# PCB.net
KiCad netlist of a schematic drawn in EAGLE
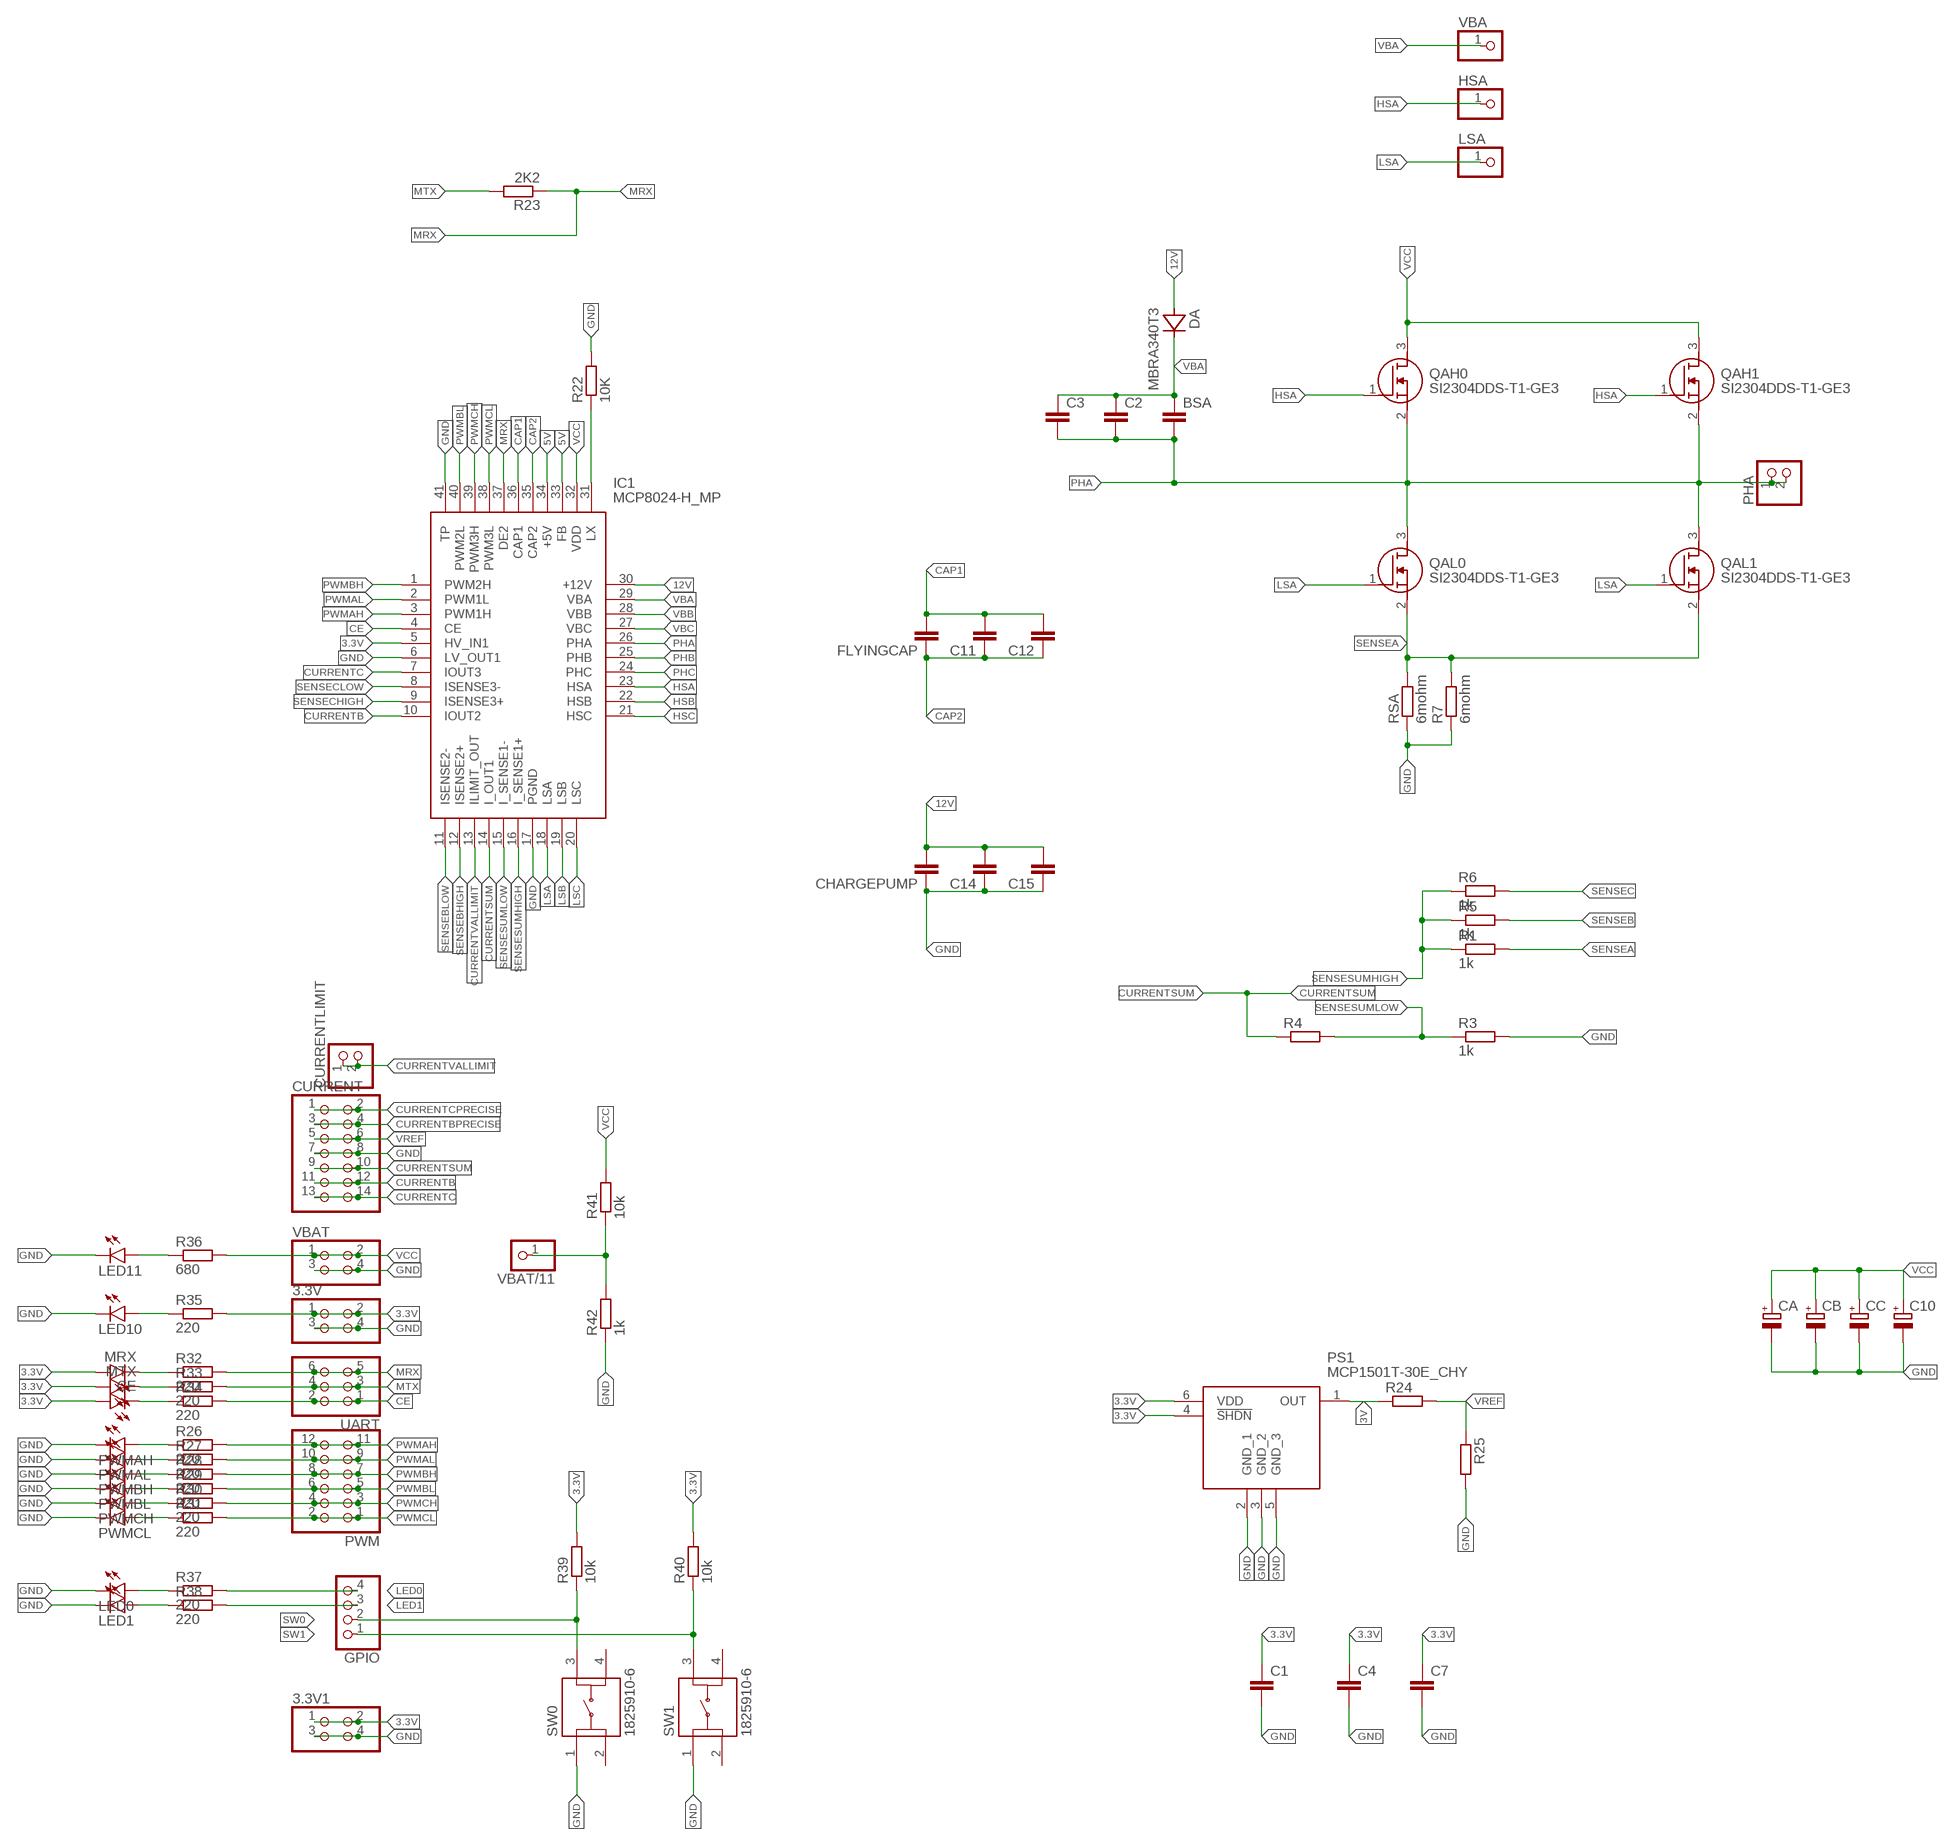
[diagram p0: schematic, sheet 1, part 1 of 2]
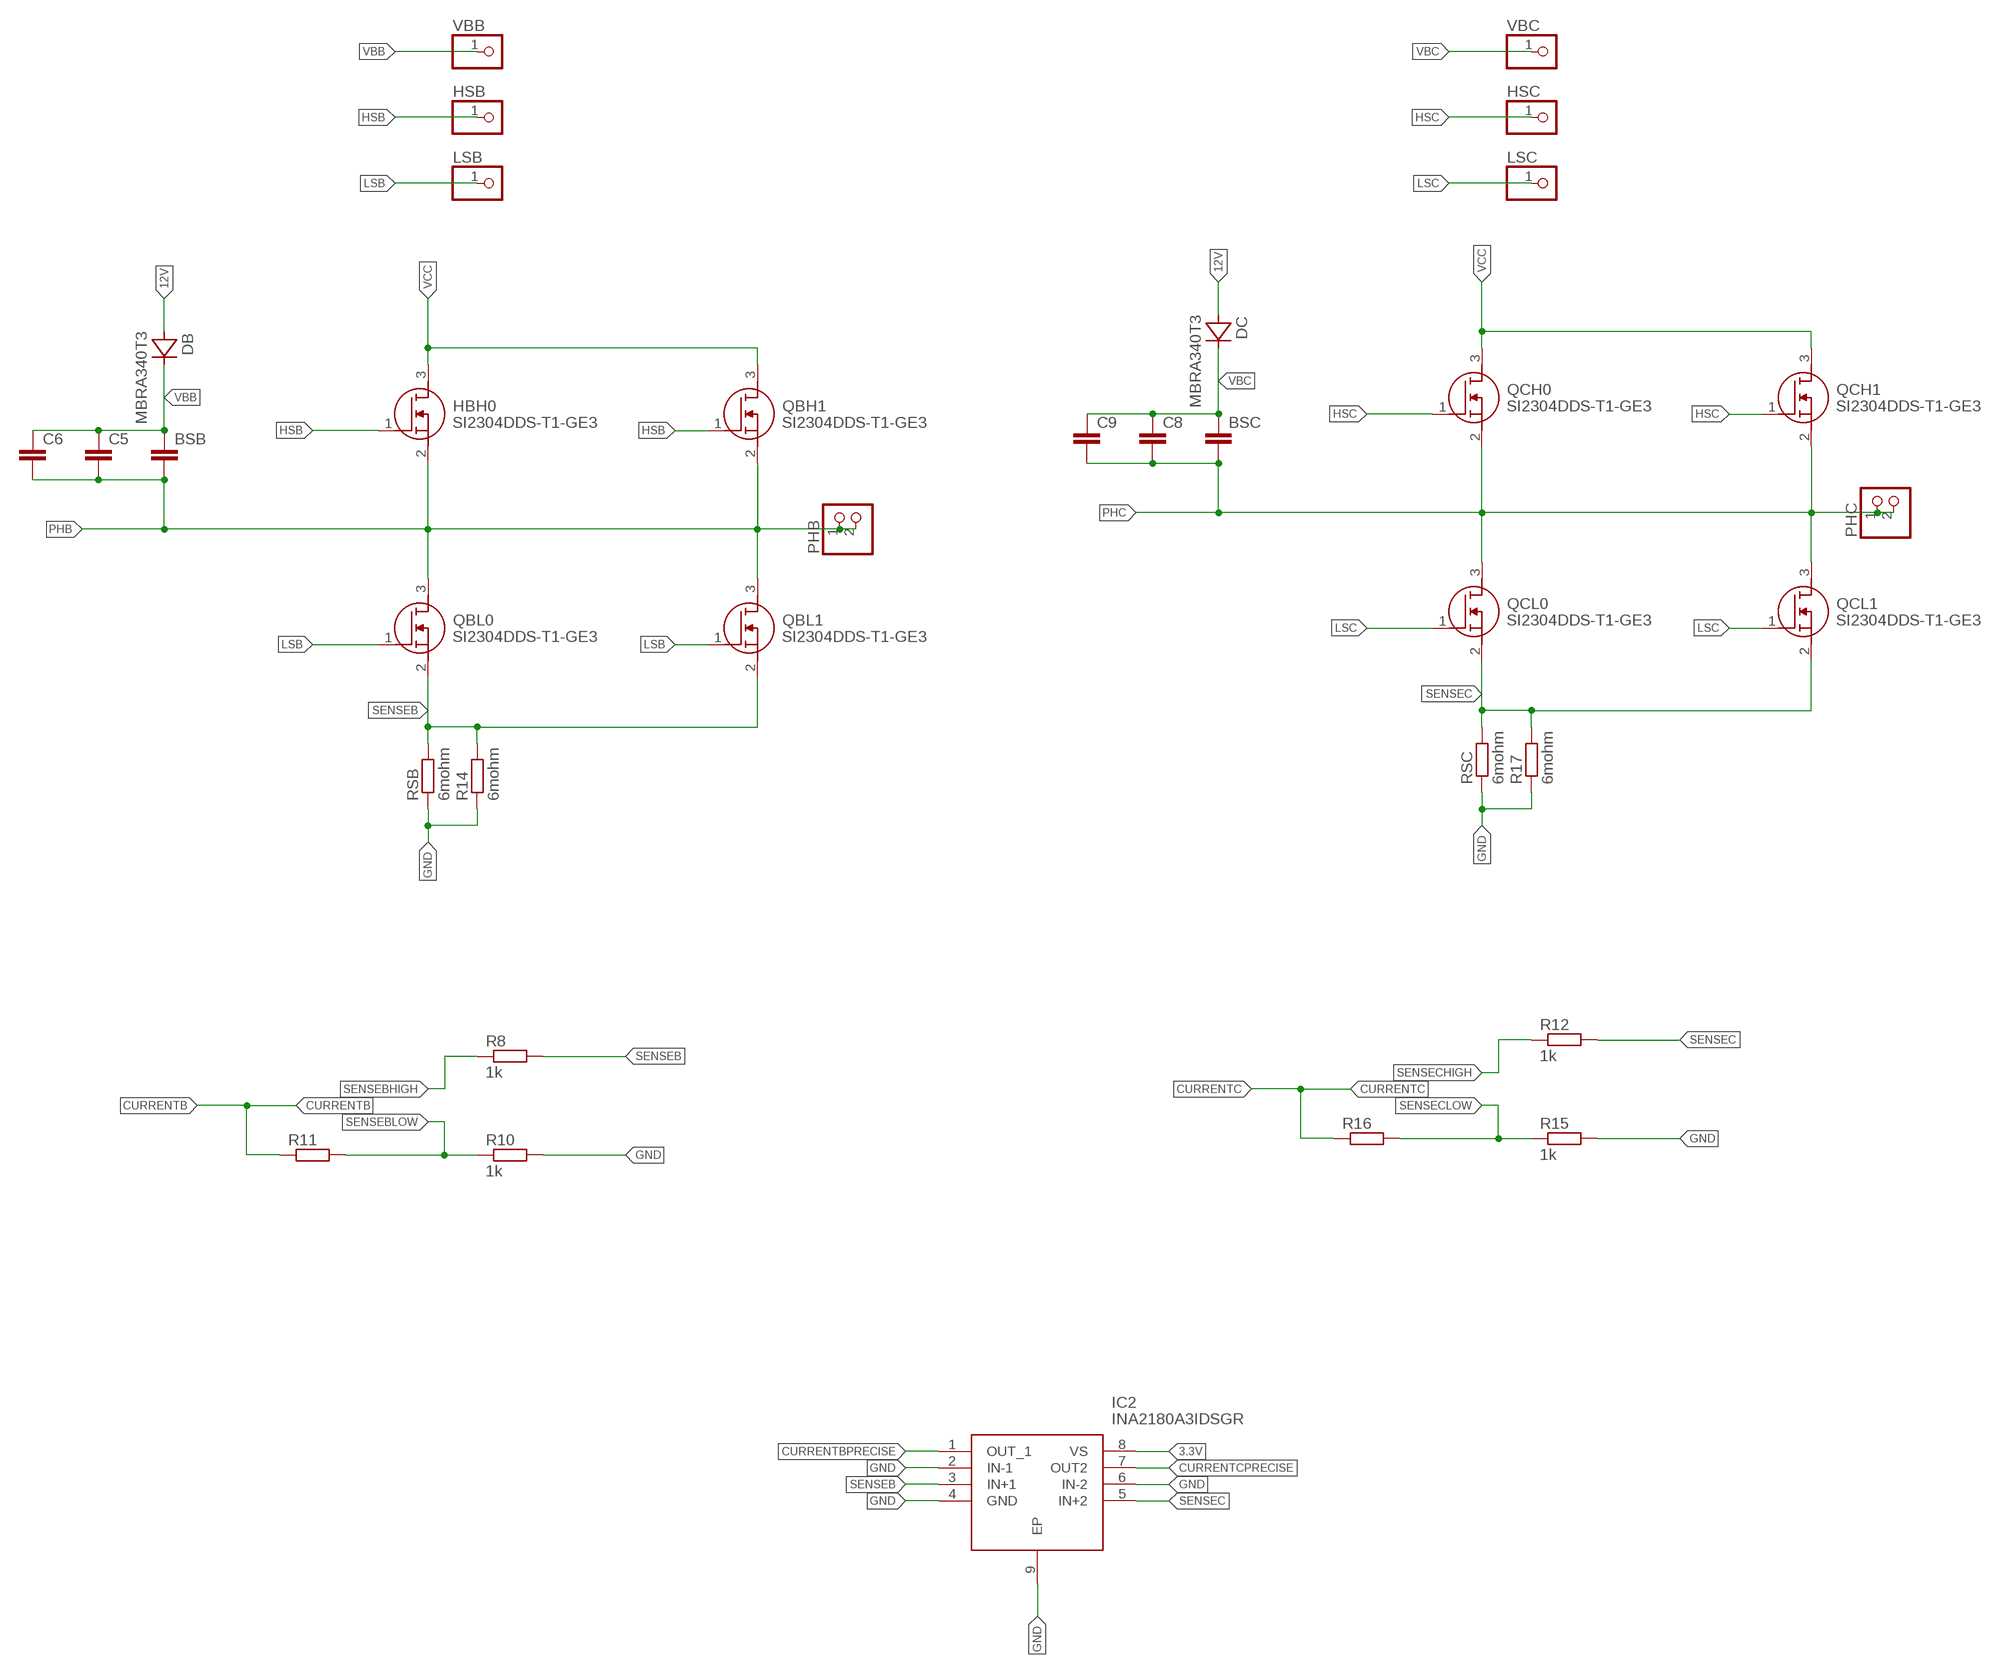
[diagram p1: schematic, sheet 1, part 2 of 2]

(export (version "E")
  (design (tool "Eeschema 10.0.6"))
  (components
    (comp (ref "3.3V")
      (value "PINHD-2X2")
      (footprint "eagle-import:2X02")
      (libsource (lib "eagle-import") (part "PINHD-2X2"))
    )
    (comp (ref "3.3V1")
      (value "PINHD-2X2")
      (footprint "eagle-import:2X02")
      (libsource (lib "eagle-import") (part "PINHD-2X2"))
    )
    (comp (ref "BSA")
      (value "C-EUC0603")
      (footprint "eagle-import:C0603")
      (libsource (lib "eagle-import") (part "C-EUC0603"))
    )
    (comp (ref "BSB")
      (value "C-EUC0603")
      (footprint "eagle-import:C0603")
      (libsource (lib "eagle-import") (part "C-EUC0603"))
    )
    (comp (ref "BSC")
      (value "C-EUC0603")
      (footprint "eagle-import:C0603")
      (libsource (lib "eagle-import") (part "C-EUC0603"))
    )
    (comp (ref "C1")
      (value "C-EUC0603")
      (footprint "eagle-import:C0603")
      (libsource (lib "eagle-import") (part "C-EUC0603"))
    )
    (comp (ref "C2")
      (value "C-EUC0603")
      (footprint "eagle-import:C0603")
      (libsource (lib "eagle-import") (part "C-EUC0603"))
    )
    (comp (ref "C3")
      (value "C-EUC0603")
      (footprint "eagle-import:C0603")
      (libsource (lib "eagle-import") (part "C-EUC0603"))
    )
    (comp (ref "C4")
      (value "C-EUC0603")
      (footprint "eagle-import:C0603")
      (libsource (lib "eagle-import") (part "C-EUC0603"))
    )
    (comp (ref "C5")
      (value "C-EUC0603")
      (footprint "eagle-import:C0603")
      (libsource (lib "eagle-import") (part "C-EUC0603"))
    )
    (comp (ref "C6")
      (value "C-EUC0603")
      (footprint "eagle-import:C0603")
      (libsource (lib "eagle-import") (part "C-EUC0603"))
    )
    (comp (ref "C7")
      (value "C-EUC0603")
      (footprint "eagle-import:C0603")
      (libsource (lib "eagle-import") (part "C-EUC0603"))
    )
    (comp (ref "C8")
      (value "C-EUC0603")
      (footprint "eagle-import:C0603")
      (libsource (lib "eagle-import") (part "C-EUC0603"))
    )
    (comp (ref "C9")
      (value "C-EUC0603")
      (footprint "eagle-import:C0603")
      (libsource (lib "eagle-import") (part "C-EUC0603"))
    )
    (comp (ref "C10")
      (value "CPOL-EUE3.5-8")
      (footprint "eagle-import:E3,5-8")
      (libsource (lib "eagle-import") (part "CPOL-EUE3.5-8"))
    )
    (comp (ref "C11")
      (value "C-EUC0603")
      (footprint "eagle-import:C0603")
      (libsource (lib "eagle-import") (part "C-EUC0603"))
    )
    (comp (ref "C12")
      (value "C-EUC0603")
      (footprint "eagle-import:C0603")
      (libsource (lib "eagle-import") (part "C-EUC0603"))
    )
    (comp (ref "C14")
      (value "C-EUC0603")
      (footprint "eagle-import:C0603")
      (libsource (lib "eagle-import") (part "C-EUC0603"))
    )
    (comp (ref "C15")
      (value "C-EUC0603")
      (footprint "eagle-import:C0603")
      (libsource (lib "eagle-import") (part "C-EUC0603"))
    )
    (comp (ref "CA")
      (value "CPOL-EUE3.5-8")
      (footprint "eagle-import:E3,5-8")
      (libsource (lib "eagle-import") (part "CPOL-EUE3.5-8"))
    )
    (comp (ref "CB")
      (value "CPOL-EUE3.5-8")
      (footprint "eagle-import:E3,5-8")
      (libsource (lib "eagle-import") (part "CPOL-EUE3.5-8"))
    )
    (comp (ref "CC")
      (value "CPOL-EUE3.5-8")
      (footprint "eagle-import:E3,5-8")
      (libsource (lib "eagle-import") (part "CPOL-EUE3.5-8"))
    )
    (comp (ref "CE")
      (value "LEDCHIPLED_0805")
      (footprint "eagle-import:CHIPLED_0805")
      (libsource (lib "eagle-import") (part "LEDCHIPLED_0805"))
    )
    (comp (ref "CHARGEPUMP")
      (value "C-EUC0603")
      (footprint "eagle-import:C0603")
      (libsource (lib "eagle-import") (part "C-EUC0603"))
    )
    (comp (ref "CURRENT")
      (value "PINHD-2X7")
      (footprint "eagle-import:2X07")
      (libsource (lib "eagle-import") (part "PINHD-2X7"))
    )
    (comp (ref "CURRENTLIMIT")
      (value "PINHD-1X2")
      (footprint "eagle-import:1X02")
      (libsource (lib "eagle-import") (part "PINHD-1X2"))
    )
    (comp (ref "DA")
      (value "MBRA340T3")
      (footprint "eagle-import:SMA")
      (libsource (lib "eagle-import") (part "MBRA340T3"))
    )
    (comp (ref "DB")
      (value "MBRA340T3")
      (footprint "eagle-import:SMA")
      (libsource (lib "eagle-import") (part "MBRA340T3"))
    )
    (comp (ref "DC")
      (value "MBRA340T3")
      (footprint "eagle-import:SMA")
      (libsource (lib "eagle-import") (part "MBRA340T3"))
    )
    (comp (ref "FLYINGCAP")
      (value "C-EUC0603")
      (footprint "eagle-import:C0603")
      (libsource (lib "eagle-import") (part "C-EUC0603"))
    )
    (comp (ref "GPIO")
      (value "PINHD-1X4")
      (footprint "eagle-import:1X04")
      (libsource (lib "eagle-import") (part "PINHD-1X4"))
    )
    (comp (ref "HBH0")
      (value "SI2304DDS-T1-GE3")
      (footprint "eagle-import:SOT95P237X112-3N")
      (fields (field (name "MOUSER_PART_NUMBER") "781-SI2304DDS-GE3"))
      (libsource (lib "eagle-import") (part "SI2304DDS-T1-GE3"))
    )
    (comp (ref "HSA")
      (value "PINHD-1X1")
      (footprint "eagle-import:1X01")
      (libsource (lib "eagle-import") (part "PINHD-1X1"))
    )
    (comp (ref "HSB")
      (value "PINHD-1X1")
      (footprint "eagle-import:1X01")
      (libsource (lib "eagle-import") (part "PINHD-1X1"))
    )
    (comp (ref "HSC")
      (value "PINHD-1X1")
      (footprint "eagle-import:1X01")
      (libsource (lib "eagle-import") (part "PINHD-1X1"))
    )
    (comp (ref "IC1")
      (value "MCP8024-H_MP")
      (footprint "eagle-import:QFN40P500X500X90-41N")
      (fields
        (field (name "MANUFACTURER_PART_NUMBER") "MCP8024-H/MP")
        (field (name "MOUSER_PART_NUMBER") "579-MCP8024-H/MP")
      )
      (libsource (lib "eagle-import") (part "MCP8024-H_MP"))
    )
    (comp (ref "IC2")
      (value "INA2180A3IDSGR")
      (footprint "eagle-import:SON50P200X200X80-9N")
      (fields (field (name "MOUSER_PART_NUMBER") "595-INA2180A3IDSGR"))
      (libsource (lib "eagle-import") (part "INA2180A3IDSGR"))
    )
    (comp (ref "LED0")
      (value "LEDCHIPLED_0805")
      (footprint "eagle-import:CHIPLED_0805")
      (libsource (lib "eagle-import") (part "LEDCHIPLED_0805"))
    )
    (comp (ref "LED1")
      (value "LEDCHIPLED_0805")
      (footprint "eagle-import:CHIPLED_0805")
      (libsource (lib "eagle-import") (part "LEDCHIPLED_0805"))
    )
    (comp (ref "LED10")
      (value "LEDCHIPLED_0805")
      (footprint "eagle-import:CHIPLED_0805")
      (libsource (lib "eagle-import") (part "LEDCHIPLED_0805"))
    )
    (comp (ref "LED11")
      (value "LEDCHIPLED_0805")
      (footprint "eagle-import:CHIPLED_0805")
      (libsource (lib "eagle-import") (part "LEDCHIPLED_0805"))
    )
    (comp (ref "LSA")
      (value "PINHD-1X1")
      (footprint "eagle-import:1X01")
      (libsource (lib "eagle-import") (part "PINHD-1X1"))
    )
    (comp (ref "LSB")
      (value "PINHD-1X1")
      (footprint "eagle-import:1X01")
      (libsource (lib "eagle-import") (part "PINHD-1X1"))
    )
    (comp (ref "LSC")
      (value "PINHD-1X1")
      (footprint "eagle-import:1X01")
      (libsource (lib "eagle-import") (part "PINHD-1X1"))
    )
    (comp (ref "MRX")
      (value "LEDCHIPLED_0805")
      (footprint "eagle-import:CHIPLED_0805")
      (libsource (lib "eagle-import") (part "LEDCHIPLED_0805"))
    )
    (comp (ref "MTX")
      (value "LEDCHIPLED_0805")
      (footprint "eagle-import:CHIPLED_0805")
      (libsource (lib "eagle-import") (part "LEDCHIPLED_0805"))
    )
    (comp (ref "PHA")
      (value "PINHD-1X2")
      (footprint "eagle-import:1X02")
      (libsource (lib "eagle-import") (part "PINHD-1X2"))
    )
    (comp (ref "PHB")
      (value "PINHD-1X2")
      (footprint "eagle-import:1X02")
      (libsource (lib "eagle-import") (part "PINHD-1X2"))
    )
    (comp (ref "PHC")
      (value "PINHD-1X2")
      (footprint "eagle-import:1X02")
      (libsource (lib "eagle-import") (part "PINHD-1X2"))
    )
    (comp (ref "PS1")
      (value "MCP1501T-30E_CHY")
      (footprint "eagle-import:SOT95P270X145-6N")
      (fields
        (field (name "MANUFACTURER_PART_NUMBER") "MCP1501T-30E/CHY")
        (field (name "MOUSER_PART_NUMBER") "579-MCP1501T-30E/CHY")
      )
      (libsource (lib "eagle-import") (part "MCP1501T-30E_CHY"))
    )
    (comp (ref "PWM")
      (value "PINHD-2X6")
      (footprint "eagle-import:2X06")
      (libsource (lib "eagle-import") (part "PINHD-2X6"))
    )
    (comp (ref "PWMAH")
      (value "LEDCHIPLED_0805")
      (footprint "eagle-import:CHIPLED_0805")
      (libsource (lib "eagle-import") (part "LEDCHIPLED_0805"))
    )
    (comp (ref "PWMAL")
      (value "LEDCHIPLED_0805")
      (footprint "eagle-import:CHIPLED_0805")
      (libsource (lib "eagle-import") (part "LEDCHIPLED_0805"))
    )
    (comp (ref "PWMBH")
      (value "LEDCHIPLED_0805")
      (footprint "eagle-import:CHIPLED_0805")
      (libsource (lib "eagle-import") (part "LEDCHIPLED_0805"))
    )
    (comp (ref "PWMBL")
      (value "LEDCHIPLED_0805")
      (footprint "eagle-import:CHIPLED_0805")
      (libsource (lib "eagle-import") (part "LEDCHIPLED_0805"))
    )
    (comp (ref "PWMCH")
      (value "LEDCHIPLED_0805")
      (footprint "eagle-import:CHIPLED_0805")
      (libsource (lib "eagle-import") (part "LEDCHIPLED_0805"))
    )
    (comp (ref "PWMCL")
      (value "LEDCHIPLED_0805")
      (footprint "eagle-import:CHIPLED_0805")
      (libsource (lib "eagle-import") (part "LEDCHIPLED_0805"))
    )
    (comp (ref "QAH0")
      (value "SI2304DDS-T1-GE3")
      (footprint "eagle-import:SOT95P237X112-3N")
      (fields (field (name "MOUSER_PART_NUMBER") "781-SI2304DDS-GE3"))
      (libsource (lib "eagle-import") (part "SI2304DDS-T1-GE3"))
    )
    (comp (ref "QAH1")
      (value "SI2304DDS-T1-GE3")
      (footprint "eagle-import:SOT95P237X112-3N")
      (fields (field (name "MOUSER_PART_NUMBER") "781-SI2304DDS-GE3"))
      (libsource (lib "eagle-import") (part "SI2304DDS-T1-GE3"))
    )
    (comp (ref "QAL0")
      (value "SI2304DDS-T1-GE3")
      (footprint "eagle-import:SOT95P237X112-3N")
      (fields (field (name "MOUSER_PART_NUMBER") "781-SI2304DDS-GE3"))
      (libsource (lib "eagle-import") (part "SI2304DDS-T1-GE3"))
    )
    (comp (ref "QAL1")
      (value "SI2304DDS-T1-GE3")
      (footprint "eagle-import:SOT95P237X112-3N")
      (fields (field (name "MOUSER_PART_NUMBER") "781-SI2304DDS-GE3"))
      (libsource (lib "eagle-import") (part "SI2304DDS-T1-GE3"))
    )
    (comp (ref "QBH1")
      (value "SI2304DDS-T1-GE3")
      (footprint "eagle-import:SOT95P237X112-3N")
      (fields (field (name "MOUSER_PART_NUMBER") "781-SI2304DDS-GE3"))
      (libsource (lib "eagle-import") (part "SI2304DDS-T1-GE3"))
    )
    (comp (ref "QBL0")
      (value "SI2304DDS-T1-GE3")
      (footprint "eagle-import:SOT95P237X112-3N")
      (fields (field (name "MOUSER_PART_NUMBER") "781-SI2304DDS-GE3"))
      (libsource (lib "eagle-import") (part "SI2304DDS-T1-GE3"))
    )
    (comp (ref "QBL1")
      (value "SI2304DDS-T1-GE3")
      (footprint "eagle-import:SOT95P237X112-3N")
      (fields (field (name "MOUSER_PART_NUMBER") "781-SI2304DDS-GE3"))
      (libsource (lib "eagle-import") (part "SI2304DDS-T1-GE3"))
    )
    (comp (ref "QCH0")
      (value "SI2304DDS-T1-GE3")
      (footprint "eagle-import:SOT95P237X112-3N")
      (fields (field (name "MOUSER_PART_NUMBER") "781-SI2304DDS-GE3"))
      (libsource (lib "eagle-import") (part "SI2304DDS-T1-GE3"))
    )
    (comp (ref "QCH1")
      (value "SI2304DDS-T1-GE3")
      (footprint "eagle-import:SOT95P237X112-3N")
      (fields (field (name "MOUSER_PART_NUMBER") "781-SI2304DDS-GE3"))
      (libsource (lib "eagle-import") (part "SI2304DDS-T1-GE3"))
    )
    (comp (ref "QCL0")
      (value "SI2304DDS-T1-GE3")
      (footprint "eagle-import:SOT95P237X112-3N")
      (fields (field (name "MOUSER_PART_NUMBER") "781-SI2304DDS-GE3"))
      (libsource (lib "eagle-import") (part "SI2304DDS-T1-GE3"))
    )
    (comp (ref "QCL1")
      (value "SI2304DDS-T1-GE3")
      (footprint "eagle-import:SOT95P237X112-3N")
      (fields (field (name "MOUSER_PART_NUMBER") "781-SI2304DDS-GE3"))
      (libsource (lib "eagle-import") (part "SI2304DDS-T1-GE3"))
    )
    (comp (ref "R1")
      (value "1k")
      (footprint "eagle-import:R0805")
      (libsource (lib "eagle-import") (part "R-EU_R0805"))
    )
    (comp (ref "R3")
      (value "1k")
      (footprint "eagle-import:R0805")
      (libsource (lib "eagle-import") (part "R-EU_R0805"))
    )
    (comp (ref "R4")
      (value "R-EU_R0805")
      (footprint "eagle-import:R0805")
      (libsource (lib "eagle-import") (part "R-EU_R0805"))
    )
    (comp (ref "R5")
      (value "1k")
      (footprint "eagle-import:R0805")
      (libsource (lib "eagle-import") (part "R-EU_R0805"))
    )
    (comp (ref "R6")
      (value "1k")
      (footprint "eagle-import:R0805")
      (libsource (lib "eagle-import") (part "R-EU_R0805"))
    )
    (comp (ref "R7")
      (value "6mohm")
      (footprint "eagle-import:R1206")
      (libsource (lib "eagle-import") (part "R-EU_R1206"))
    )
    (comp (ref "R8")
      (value "1k")
      (footprint "eagle-import:R0805")
      (libsource (lib "eagle-import") (part "R-EU_R0805"))
    )
    (comp (ref "R10")
      (value "1k")
      (footprint "eagle-import:R0805")
      (libsource (lib "eagle-import") (part "R-EU_R0805"))
    )
    (comp (ref "R11")
      (value "R-EU_R0805")
      (footprint "eagle-import:R0805")
      (libsource (lib "eagle-import") (part "R-EU_R0805"))
    )
    (comp (ref "R12")
      (value "1k")
      (footprint "eagle-import:R0805")
      (libsource (lib "eagle-import") (part "R-EU_R0805"))
    )
    (comp (ref "R14")
      (value "6mohm")
      (footprint "eagle-import:R1206")
      (libsource (lib "eagle-import") (part "R-EU_R1206"))
    )
    (comp (ref "R15")
      (value "1k")
      (footprint "eagle-import:R0805")
      (libsource (lib "eagle-import") (part "R-EU_R0805"))
    )
    (comp (ref "R16")
      (value "R-EU_R0805")
      (footprint "eagle-import:R0805")
      (libsource (lib "eagle-import") (part "R-EU_R0805"))
    )
    (comp (ref "R17")
      (value "6mohm")
      (footprint "eagle-import:R1206")
      (libsource (lib "eagle-import") (part "R-EU_R1206"))
    )
    (comp (ref "R22")
      (value "10K")
      (footprint "eagle-import:R0805")
      (libsource (lib "eagle-import") (part "R-EU_R0805"))
    )
    (comp (ref "R23")
      (value "2K2")
      (footprint "eagle-import:R0805")
      (libsource (lib "eagle-import") (part "R-EU_R0805"))
    )
    (comp (ref "R24")
      (value "R-EU_R0805")
      (footprint "eagle-import:R0805")
      (libsource (lib "eagle-import") (part "R-EU_R0805"))
    )
    (comp (ref "R25")
      (value "R-EU_R0805")
      (footprint "eagle-import:R0805")
      (libsource (lib "eagle-import") (part "R-EU_R0805"))
    )
    (comp (ref "R26")
      (value "220")
      (footprint "eagle-import:R0805")
      (libsource (lib "eagle-import") (part "R-EU_R0805"))
    )
    (comp (ref "R27")
      (value "220")
      (footprint "eagle-import:R0805")
      (libsource (lib "eagle-import") (part "R-EU_R0805"))
    )
    (comp (ref "R28")
      (value "220")
      (footprint "eagle-import:R0805")
      (libsource (lib "eagle-import") (part "R-EU_R0805"))
    )
    (comp (ref "R29")
      (value "220")
      (footprint "eagle-import:R0805")
      (libsource (lib "eagle-import") (part "R-EU_R0805"))
    )
    (comp (ref "R30")
      (value "220")
      (footprint "eagle-import:R0805")
      (libsource (lib "eagle-import") (part "R-EU_R0805"))
    )
    (comp (ref "R31")
      (value "220")
      (footprint "eagle-import:R0805")
      (libsource (lib "eagle-import") (part "R-EU_R0805"))
    )
    (comp (ref "R32")
      (value "220")
      (footprint "eagle-import:R0805")
      (libsource (lib "eagle-import") (part "R-EU_R0805"))
    )
    (comp (ref "R33")
      (value "220")
      (footprint "eagle-import:R0805")
      (libsource (lib "eagle-import") (part "R-EU_R0805"))
    )
    (comp (ref "R34")
      (value "220")
      (footprint "eagle-import:R0805")
      (libsource (lib "eagle-import") (part "R-EU_R0805"))
    )
    (comp (ref "R35")
      (value "220")
      (footprint "eagle-import:R0805")
      (libsource (lib "eagle-import") (part "R-EU_R0805"))
    )
    (comp (ref "R36")
      (value "680")
      (footprint "eagle-import:R0805")
      (libsource (lib "eagle-import") (part "R-EU_R0805"))
    )
    (comp (ref "R37")
      (value "220")
      (footprint "eagle-import:R0805")
      (libsource (lib "eagle-import") (part "R-EU_R0805"))
    )
    (comp (ref "R38")
      (value "220")
      (footprint "eagle-import:R0805")
      (libsource (lib "eagle-import") (part "R-EU_R0805"))
    )
    (comp (ref "R39")
      (value "10k")
      (footprint "eagle-import:R0805")
      (libsource (lib "eagle-import") (part "R-EU_R0805"))
    )
    (comp (ref "R40")
      (value "10k")
      (footprint "eagle-import:R0805")
      (libsource (lib "eagle-import") (part "R-EU_R0805"))
    )
    (comp (ref "R41")
      (value "10k")
      (footprint "eagle-import:R0805")
      (libsource (lib "eagle-import") (part "R-EU_R0805"))
    )
    (comp (ref "R42")
      (value "1k")
      (footprint "eagle-import:R0805")
      (libsource (lib "eagle-import") (part "R-EU_R0805"))
    )
    (comp (ref "RSA")
      (value "6mohm")
      (footprint "eagle-import:R1206")
      (libsource (lib "eagle-import") (part "R-EU_R1206"))
    )
    (comp (ref "RSB")
      (value "6mohm")
      (footprint "eagle-import:R1206")
      (libsource (lib "eagle-import") (part "R-EU_R1206"))
    )
    (comp (ref "RSC")
      (value "6mohm")
      (footprint "eagle-import:R1206")
      (libsource (lib "eagle-import") (part "R-EU_R1206"))
    )
    (comp (ref "SW0")
      (value "1825910-6")
      (footprint "eagle-import:1825910-6")
      (fields
        (field (name "DIGIKEY_PART_NUMBER") "450-1650-ND")
        (field (name "MANUFACTURER") "TE Connectivity ALCOSWITCH Switches")
        (field (name "CREATED_BY") " PCBLayout.com")
      )
      (libsource (lib "eagle-import") (part "1825910-6"))
    )
    (comp (ref "SW1")
      (value "1825910-6")
      (footprint "eagle-import:1825910-6")
      (fields
        (field (name "DIGIKEY_PART_NUMBER") "450-1650-ND")
        (field (name "MANUFACTURER") "TE Connectivity ALCOSWITCH Switches")
        (field (name "CREATED_BY") " PCBLayout.com")
      )
      (libsource (lib "eagle-import") (part "1825910-6"))
    )
    (comp (ref "UART")
      (value "PINHD-2X3")
      (footprint "eagle-import:2X03")
      (libsource (lib "eagle-import") (part "PINHD-2X3"))
    )
    (comp (ref "VBA")
      (value "PINHD-1X1")
      (footprint "eagle-import:1X01")
      (libsource (lib "eagle-import") (part "PINHD-1X1"))
    )
    (comp (ref "VBAT")
      (value "PINHD-2X2")
      (footprint "eagle-import:2X02")
      (libsource (lib "eagle-import") (part "PINHD-2X2"))
    )
    (comp (ref "VBAT/11")
      (value "PINHD-1X1")
      (footprint "eagle-import:1X01")
      (libsource (lib "eagle-import") (part "PINHD-1X1"))
    )
    (comp (ref "VBB")
      (value "PINHD-1X1")
      (footprint "eagle-import:1X01")
      (libsource (lib "eagle-import") (part "PINHD-1X1"))
    )
    (comp (ref "VBC")
      (value "PINHD-1X1")
      (footprint "eagle-import:1X01")
      (libsource (lib "eagle-import") (part "PINHD-1X1"))
    )
  )
  (nets
    (net (code "1") (name "3.3V") (class "Default")
      (node (ref "3.3V") (pin "1") (pinfunction "1_1") (pintype "passive"))
      (node (ref "3.3V") (pin "2") (pinfunction "2_2") (pintype "passive"))
      (node (ref "3.3V1") (pin "1") (pinfunction "1_1") (pintype "passive"))
      (node (ref "3.3V1") (pin "2") (pinfunction "2_2") (pintype "passive"))
      (node (ref "C1") (pin "1") (pinfunction "1_1") (pintype "passive"))
      (node (ref "C4") (pin "1") (pinfunction "1_1") (pintype "passive"))
      (node (ref "C7") (pin "1") (pinfunction "1_1") (pintype "passive"))
      (node (ref "CE") (pin "A") (pinfunction "A_A") (pintype "passive"))
      (node (ref "IC1") (pin "5") (pinfunction "HV_IN1_5") (pintype "input"))
      (node (ref "IC2") (pin "8") (pinfunction "VS_8") (pintype "bidirectional"))
      (node (ref "MRX") (pin "A") (pinfunction "A_A") (pintype "passive"))
      (node (ref "MTX") (pin "A") (pinfunction "A_A") (pintype "passive"))
      (node (ref "PS1") (pin "4") (pinfunction "~{SHDN}_4") (pintype "bidirectional"))
      (node (ref "PS1") (pin "6") (pinfunction "VDD_6") (pintype "bidirectional"))
      (node (ref "R35") (pin "2") (pinfunction "2_2") (pintype "passive"))
      (node (ref "R39") (pin "2") (pinfunction "2_2") (pintype "passive"))
      (node (ref "R40") (pin "2") (pinfunction "2_2") (pintype "passive"))
    )
    (net (code "2") (name "3V") (class "Default")
      (node (ref "PS1") (pin "1") (pinfunction "OUT_1") (pintype "bidirectional"))
      (node (ref "R24") (pin "1") (pinfunction "1_1") (pintype "passive"))
    )
    (net (code "3") (name "5V") (class "Default")
      (node (ref "IC1") (pin "33") (pinfunction "FB_33") (pintype "bidirectional"))
      (node (ref "IC1") (pin "34") (pinfunction "+5V_34") (pintype "bidirectional"))
    )
    (net (code "4") (name "12V") (class "Default")
      (node (ref "C14") (pin "2") (pinfunction "2_2") (pintype "passive"))
      (node (ref "C15") (pin "2") (pinfunction "2_2") (pintype "passive"))
      (node (ref "CHARGEPUMP") (pin "2") (pinfunction "2_2") (pintype "passive"))
      (node (ref "DA") (pin "A") (pinfunction "A_A") (pintype "passive"))
      (node (ref "DB") (pin "A") (pinfunction "A_A") (pintype "passive"))
      (node (ref "DC") (pin "A") (pinfunction "A_A") (pintype "passive"))
      (node (ref "IC1") (pin "30") (pinfunction "+12V_30") (pintype "bidirectional"))
    )
    (net (code "5") (name "CAP1") (class "Default")
      (node (ref "C11") (pin "2") (pinfunction "2_2") (pintype "passive"))
      (node (ref "C12") (pin "2") (pinfunction "2_2") (pintype "passive"))
      (node (ref "FLYINGCAP") (pin "2") (pinfunction "2_2") (pintype "passive"))
      (node (ref "IC1") (pin "36") (pinfunction "CAP1_36") (pintype "bidirectional"))
    )
    (net (code "6") (name "CAP2") (class "Default")
      (node (ref "C11") (pin "1") (pinfunction "1_1") (pintype "passive"))
      (node (ref "C12") (pin "1") (pinfunction "1_1") (pintype "passive"))
      (node (ref "FLYINGCAP") (pin "1") (pinfunction "1_1") (pintype "passive"))
      (node (ref "IC1") (pin "35") (pinfunction "CAP2_35") (pintype "bidirectional"))
    )
    (net (code "7") (name "CE") (class "Default")
      (node (ref "IC1") (pin "4") (pinfunction "CE_4") (pintype "bidirectional"))
      (node (ref "R34") (pin "2") (pinfunction "2_2") (pintype "passive"))
      (node (ref "UART") (pin "1") (pinfunction "1_1") (pintype "passive"))
      (node (ref "UART") (pin "2") (pinfunction "2_2") (pintype "passive"))
    )
    (net (code "8") (name "CURRENTB") (class "Default")
      (node (ref "CURRENT") (pin "11") (pinfunction "11_11") (pintype "passive"))
      (node (ref "CURRENT") (pin "12") (pinfunction "12_12") (pintype "passive"))
      (node (ref "IC1") (pin "10") (pinfunction "IOUT2_10") (pintype "bidirectional"))
      (node (ref "R11") (pin "1") (pinfunction "1_1") (pintype "passive"))
    )
    (net (code "9") (name "CURRENTBPRECISE") (class "Default")
      (node (ref "CURRENT") (pin "3") (pinfunction "3_3") (pintype "passive"))
      (node (ref "CURRENT") (pin "4") (pinfunction "4_4") (pintype "passive"))
      (node (ref "IC2") (pin "1") (pinfunction "OUT_1_1") (pintype "bidirectional"))
    )
    (net (code "10") (name "CURRENTC") (class "Default")
      (node (ref "CURRENT") (pin "13") (pinfunction "13_13") (pintype "passive"))
      (node (ref "CURRENT") (pin "14") (pinfunction "14_14") (pintype "passive"))
      (node (ref "IC1") (pin "7") (pinfunction "IOUT3_7") (pintype "bidirectional"))
      (node (ref "R16") (pin "1") (pinfunction "1_1") (pintype "passive"))
    )
    (net (code "11") (name "CURRENTCPRECISE") (class "Default")
      (node (ref "CURRENT") (pin "1") (pinfunction "1_1") (pintype "passive"))
      (node (ref "CURRENT") (pin "2") (pinfunction "2_2") (pintype "passive"))
      (node (ref "IC2") (pin "7") (pinfunction "OUT2_7") (pintype "bidirectional"))
    )
    (net (code "12") (name "CURRENTSUM") (class "Default")
      (node (ref "CURRENT") (pin "10") (pinfunction "10_10") (pintype "passive"))
      (node (ref "CURRENT") (pin "9") (pinfunction "9_9") (pintype "passive"))
      (node (ref "IC1") (pin "14") (pinfunction "I_OUT1_14") (pintype "output"))
      (node (ref "R4") (pin "1") (pinfunction "1_1") (pintype "passive"))
    )
    (net (code "13") (name "CURRENTVALLIMIT") (class "Default")
      (node (ref "CURRENTLIMIT") (pin "1") (pinfunction "1_1") (pintype "passive"))
      (node (ref "CURRENTLIMIT") (pin "2") (pinfunction "2_2") (pintype "passive"))
      (node (ref "IC1") (pin "13") (pinfunction "ILIMIT_OUT_13") (pintype "output"))
    )
    (net (code "14") (name "GND") (class "Default")
      (node (ref "3.3V") (pin "3") (pinfunction "3_3") (pintype "passive"))
      (node (ref "3.3V") (pin "4") (pinfunction "4_4") (pintype "passive"))
      (node (ref "3.3V1") (pin "3") (pinfunction "3_3") (pintype "passive"))
      (node (ref "3.3V1") (pin "4") (pinfunction "4_4") (pintype "passive"))
      (node (ref "C1") (pin "2") (pinfunction "2_2") (pintype "passive"))
      (node (ref "C10") (pin "-") (pinfunction "-_-") (pintype "passive"))
      (node (ref "C14") (pin "1") (pinfunction "1_1") (pintype "passive"))
      (node (ref "C15") (pin "1") (pinfunction "1_1") (pintype "passive"))
      (node (ref "C4") (pin "2") (pinfunction "2_2") (pintype "passive"))
      (node (ref "C7") (pin "2") (pinfunction "2_2") (pintype "passive"))
      (node (ref "CA") (pin "-") (pinfunction "-_-") (pintype "passive"))
      (node (ref "CB") (pin "-") (pinfunction "-_-") (pintype "passive"))
      (node (ref "CC") (pin "-") (pinfunction "-_-") (pintype "passive"))
      (node (ref "CHARGEPUMP") (pin "1") (pinfunction "1_1") (pintype "passive"))
      (node (ref "CURRENT") (pin "7") (pinfunction "7_7") (pintype "passive"))
      (node (ref "CURRENT") (pin "8") (pinfunction "8_8") (pintype "passive"))
      (node (ref "IC1") (pin "17") (pinfunction "PGND_17") (pintype "power_in"))
      (node (ref "IC1") (pin "41") (pinfunction "TP_41") (pintype "bidirectional"))
      (node (ref "IC1") (pin "6") (pinfunction "LV_OUT1_6") (pintype "output"))
      (node (ref "IC2") (pin "2") (pinfunction "IN-1_2") (pintype "bidirectional"))
      (node (ref "IC2") (pin "4") (pinfunction "GND_4") (pintype "bidirectional"))
      (node (ref "IC2") (pin "6") (pinfunction "IN-2_6") (pintype "bidirectional"))
      (node (ref "IC2") (pin "9") (pinfunction "EP_9") (pintype "bidirectional"))
      (node (ref "LED0") (pin "C") (pinfunction "C_C") (pintype "passive"))
      (node (ref "LED1") (pin "C") (pinfunction "C_C") (pintype "passive"))
      (node (ref "LED10") (pin "C") (pinfunction "C_C") (pintype "passive"))
      (node (ref "LED11") (pin "C") (pinfunction "C_C") (pintype "passive"))
      (node (ref "PS1") (pin "2") (pinfunction "GND_1_2") (pintype "bidirectional"))
      (node (ref "PS1") (pin "3") (pinfunction "GND_2_3") (pintype "bidirectional"))
      (node (ref "PS1") (pin "5") (pinfunction "GND_3_5") (pintype "bidirectional"))
      (node (ref "PWMAH") (pin "C") (pinfunction "C_C") (pintype "passive"))
      (node (ref "PWMAL") (pin "C") (pinfunction "C_C") (pintype "passive"))
      (node (ref "PWMBH") (pin "C") (pinfunction "C_C") (pintype "passive"))
      (node (ref "PWMBL") (pin "C") (pinfunction "C_C") (pintype "passive"))
      (node (ref "PWMCH") (pin "C") (pinfunction "C_C") (pintype "passive"))
      (node (ref "PWMCL") (pin "C") (pinfunction "C_C") (pintype "passive"))
      (node (ref "R10") (pin "2") (pinfunction "2_2") (pintype "passive"))
      (node (ref "R14") (pin "1") (pinfunction "1_1") (pintype "passive"))
      (node (ref "R15") (pin "2") (pinfunction "2_2") (pintype "passive"))
      (node (ref "R17") (pin "1") (pinfunction "1_1") (pintype "passive"))
      (node (ref "R22") (pin "2") (pinfunction "2_2") (pintype "passive"))
      (node (ref "R25") (pin "2") (pinfunction "2_2") (pintype "passive"))
      (node (ref "R3") (pin "2") (pinfunction "2_2") (pintype "passive"))
      (node (ref "R42") (pin "1") (pinfunction "1_1") (pintype "passive"))
      (node (ref "R7") (pin "1") (pinfunction "1_1") (pintype "passive"))
      (node (ref "RSA") (pin "1") (pinfunction "1_1") (pintype "passive"))
      (node (ref "RSB") (pin "1") (pinfunction "1_1") (pintype "passive"))
      (node (ref "RSC") (pin "1") (pinfunction "1_1") (pintype "passive"))
      (node (ref "SW0") (pin "1") (pinfunction "1_1") (pintype "passive"))
      (node (ref "SW1") (pin "1") (pinfunction "1_1") (pintype "passive"))
      (node (ref "VBAT") (pin "3") (pinfunction "3_3") (pintype "passive"))
      (node (ref "VBAT") (pin "4") (pinfunction "4_4") (pintype "passive"))
    )
    (net (code "15") (name "HSA") (class "Default")
      (node (ref "HSA") (pin "1") (pinfunction "1_1") (pintype "passive"))
      (node (ref "IC1") (pin "23") (pinfunction "HSA_23") (pintype "bidirectional"))
      (node (ref "QAH0") (pin "1") (pinfunction "G_1") (pintype "bidirectional"))
      (node (ref "QAH1") (pin "1") (pinfunction "G_1") (pintype "bidirectional"))
    )
    (net (code "16") (name "HSB") (class "Default")
      (node (ref "HBH0") (pin "1") (pinfunction "G_1") (pintype "bidirectional"))
      (node (ref "HSB") (pin "1") (pinfunction "1_1") (pintype "passive"))
      (node (ref "IC1") (pin "22") (pinfunction "HSB_22") (pintype "bidirectional"))
      (node (ref "QBH1") (pin "1") (pinfunction "G_1") (pintype "bidirectional"))
    )
    (net (code "17") (name "HSC") (class "Default")
      (node (ref "HSC") (pin "1") (pinfunction "1_1") (pintype "passive"))
      (node (ref "IC1") (pin "21") (pinfunction "HSC_21") (pintype "bidirectional"))
      (node (ref "QCH0") (pin "1") (pinfunction "G_1") (pintype "bidirectional"))
      (node (ref "QCH1") (pin "1") (pinfunction "G_1") (pintype "bidirectional"))
    )
    (net (code "18") (name "LED0") (class "Default")
      (node (ref "GPIO") (pin "4") (pinfunction "4_4") (pintype "passive"))
      (node (ref "R37") (pin "2") (pinfunction "2_2") (pintype "passive"))
    )
    (net (code "19") (name "LED1") (class "Default")
      (node (ref "GPIO") (pin "3") (pinfunction "3_3") (pintype "passive"))
      (node (ref "R38") (pin "2") (pinfunction "2_2") (pintype "passive"))
    )
    (net (code "20") (name "LSA") (class "Default")
      (node (ref "IC1") (pin "18") (pinfunction "LSA_18") (pintype "bidirectional"))
      (node (ref "LSA") (pin "1") (pinfunction "1_1") (pintype "passive"))
      (node (ref "QAL0") (pin "1") (pinfunction "G_1") (pintype "bidirectional"))
      (node (ref "QAL1") (pin "1") (pinfunction "G_1") (pintype "bidirectional"))
    )
    (net (code "21") (name "LSB") (class "Default")
      (node (ref "IC1") (pin "19") (pinfunction "LSB_19") (pintype "bidirectional"))
      (node (ref "LSB") (pin "1") (pinfunction "1_1") (pintype "passive"))
      (node (ref "QBL0") (pin "1") (pinfunction "G_1") (pintype "bidirectional"))
      (node (ref "QBL1") (pin "1") (pinfunction "G_1") (pintype "bidirectional"))
    )
    (net (code "22") (name "LSC") (class "Default")
      (node (ref "IC1") (pin "20") (pinfunction "LSC_20") (pintype "bidirectional"))
      (node (ref "LSC") (pin "1") (pinfunction "1_1") (pintype "passive"))
      (node (ref "QCL0") (pin "1") (pinfunction "G_1") (pintype "bidirectional"))
      (node (ref "QCL1") (pin "1") (pinfunction "G_1") (pintype "bidirectional"))
    )
    (net (code "23") (name "MRX") (class "Default")
      (node (ref "IC1") (pin "37") (pinfunction "DE2_37") (pintype "bidirectional"))
      (node (ref "R23") (pin "1") (pinfunction "1_1") (pintype "passive"))
      (node (ref "R32") (pin "2") (pinfunction "2_2") (pintype "passive"))
      (node (ref "UART") (pin "5") (pinfunction "5_5") (pintype "passive"))
      (node (ref "UART") (pin "6") (pinfunction "6_6") (pintype "passive"))
    )
    (net (code "24") (name "MTX") (class "Default")
      (node (ref "R23") (pin "2") (pinfunction "2_2") (pintype "passive"))
      (node (ref "R33") (pin "2") (pinfunction "2_2") (pintype "passive"))
      (node (ref "UART") (pin "3") (pinfunction "3_3") (pintype "passive"))
      (node (ref "UART") (pin "4") (pinfunction "4_4") (pintype "passive"))
    )
    (net (code "25") (name "Net-(CE-PadC)") (class "Default")
      (node (ref "CE") (pin "C") (pinfunction "C_C") (pintype "passive"))
      (node (ref "R34") (pin "1") (pinfunction "1_1") (pintype "passive"))
    )
    (net (code "26") (name "Net-(IC1-LX)") (class "Default")
      (node (ref "IC1") (pin "31") (pinfunction "LX_31") (pintype "bidirectional"))
      (node (ref "R22") (pin "1") (pinfunction "1_1") (pintype "passive"))
    )
    (net (code "27") (name "Net-(LED0-PadA)") (class "Default")
      (node (ref "LED0") (pin "A") (pinfunction "A_A") (pintype "passive"))
      (node (ref "R37") (pin "1") (pinfunction "1_1") (pintype "passive"))
    )
    (net (code "28") (name "Net-(LED1-PadA)") (class "Default")
      (node (ref "LED1") (pin "A") (pinfunction "A_A") (pintype "passive"))
      (node (ref "R38") (pin "1") (pinfunction "1_1") (pintype "passive"))
    )
    (net (code "29") (name "Net-(LED10-PadA)") (class "Default")
      (node (ref "LED10") (pin "A") (pinfunction "A_A") (pintype "passive"))
      (node (ref "R35") (pin "1") (pinfunction "1_1") (pintype "passive"))
    )
    (net (code "30") (name "Net-(LED11-PadA)") (class "Default")
      (node (ref "LED11") (pin "A") (pinfunction "A_A") (pintype "passive"))
      (node (ref "R36") (pin "1") (pinfunction "1_1") (pintype "passive"))
    )
    (net (code "31") (name "Net-(MRX-PadC)") (class "Default")
      (node (ref "MRX") (pin "C") (pinfunction "C_C") (pintype "passive"))
      (node (ref "R32") (pin "1") (pinfunction "1_1") (pintype "passive"))
    )
    (net (code "32") (name "Net-(MTX-PadC)") (class "Default")
      (node (ref "MTX") (pin "C") (pinfunction "C_C") (pintype "passive"))
      (node (ref "R33") (pin "1") (pinfunction "1_1") (pintype "passive"))
    )
    (net (code "33") (name "Net-(PWMAH-PadA)") (class "Default")
      (node (ref "PWMAH") (pin "A") (pinfunction "A_A") (pintype "passive"))
      (node (ref "R26") (pin "1") (pinfunction "1_1") (pintype "passive"))
    )
    (net (code "34") (name "Net-(PWMAL-PadA)") (class "Default")
      (node (ref "PWMAL") (pin "A") (pinfunction "A_A") (pintype "passive"))
      (node (ref "R27") (pin "1") (pinfunction "1_1") (pintype "passive"))
    )
    (net (code "35") (name "Net-(PWMBH-PadA)") (class "Default")
      (node (ref "PWMBH") (pin "A") (pinfunction "A_A") (pintype "passive"))
      (node (ref "R28") (pin "1") (pinfunction "1_1") (pintype "passive"))
    )
    (net (code "36") (name "Net-(PWMBL-PadA)") (class "Default")
      (node (ref "PWMBL") (pin "A") (pinfunction "A_A") (pintype "passive"))
      (node (ref "R29") (pin "1") (pinfunction "1_1") (pintype "passive"))
    )
    (net (code "37") (name "Net-(PWMCH-PadA)") (class "Default")
      (node (ref "PWMCH") (pin "A") (pinfunction "A_A") (pintype "passive"))
      (node (ref "R30") (pin "1") (pinfunction "1_1") (pintype "passive"))
    )
    (net (code "38") (name "Net-(PWMCL-PadA)") (class "Default")
      (node (ref "PWMCL") (pin "A") (pinfunction "A_A") (pintype "passive"))
      (node (ref "R31") (pin "1") (pinfunction "1_1") (pintype "passive"))
    )
    (net (code "39") (name "Net-(R41-Pad1)") (class "Default")
      (node (ref "R41") (pin "1") (pinfunction "1_1") (pintype "passive"))
      (node (ref "R42") (pin "2") (pinfunction "2_2") (pintype "passive"))
      (node (ref "VBAT/11") (pin "1") (pinfunction "1_1") (pintype "passive"))
    )
    (net (code "40") (name "PHA") (class "Default")
      (node (ref "BSA") (pin "2") (pinfunction "2_2") (pintype "passive"))
      (node (ref "C2") (pin "2") (pinfunction "2_2") (pintype "passive"))
      (node (ref "C3") (pin "2") (pinfunction "2_2") (pintype "passive"))
      (node (ref "IC1") (pin "26") (pinfunction "PHA_26") (pintype "bidirectional"))
      (node (ref "PHA") (pin "1") (pinfunction "1_1") (pintype "passive"))
      (node (ref "PHA") (pin "2") (pinfunction "2_2") (pintype "passive"))
      (node (ref "QAH0") (pin "2") (pinfunction "S_2") (pintype "bidirectional"))
      (node (ref "QAH1") (pin "2") (pinfunction "S_2") (pintype "bidirectional"))
      (node (ref "QAL0") (pin "3") (pinfunction "D_3") (pintype "bidirectional"))
      (node (ref "QAL1") (pin "3") (pinfunction "D_3") (pintype "bidirectional"))
    )
    (net (code "41") (name "PHB") (class "Default")
      (node (ref "BSB") (pin "2") (pinfunction "2_2") (pintype "passive"))
      (node (ref "C5") (pin "2") (pinfunction "2_2") (pintype "passive"))
      (node (ref "C6") (pin "2") (pinfunction "2_2") (pintype "passive"))
      (node (ref "HBH0") (pin "2") (pinfunction "S_2") (pintype "bidirectional"))
      (node (ref "IC1") (pin "25") (pinfunction "PHB_25") (pintype "bidirectional"))
      (node (ref "PHB") (pin "1") (pinfunction "1_1") (pintype "passive"))
      (node (ref "PHB") (pin "2") (pinfunction "2_2") (pintype "passive"))
      (node (ref "QBH1") (pin "2") (pinfunction "S_2") (pintype "bidirectional"))
      (node (ref "QBL0") (pin "3") (pinfunction "D_3") (pintype "bidirectional"))
      (node (ref "QBL1") (pin "3") (pinfunction "D_3") (pintype "bidirectional"))
    )
    (net (code "42") (name "PHC") (class "Default")
      (node (ref "BSC") (pin "2") (pinfunction "2_2") (pintype "passive"))
      (node (ref "C8") (pin "2") (pinfunction "2_2") (pintype "passive"))
      (node (ref "C9") (pin "2") (pinfunction "2_2") (pintype "passive"))
      (node (ref "IC1") (pin "24") (pinfunction "PHC_24") (pintype "bidirectional"))
      (node (ref "PHC") (pin "1") (pinfunction "1_1") (pintype "passive"))
      (node (ref "PHC") (pin "2") (pinfunction "2_2") (pintype "passive"))
      (node (ref "QCH0") (pin "2") (pinfunction "S_2") (pintype "bidirectional"))
      (node (ref "QCH1") (pin "2") (pinfunction "S_2") (pintype "bidirectional"))
      (node (ref "QCL0") (pin "3") (pinfunction "D_3") (pintype "bidirectional"))
      (node (ref "QCL1") (pin "3") (pinfunction "D_3") (pintype "bidirectional"))
    )
    (net (code "43") (name "PWMAH") (class "Default")
      (node (ref "IC1") (pin "3") (pinfunction "PWM1H_3") (pintype "bidirectional"))
      (node (ref "PWM") (pin "11") (pinfunction "11_11") (pintype "passive"))
      (node (ref "PWM") (pin "12") (pinfunction "12_12") (pintype "passive"))
      (node (ref "R26") (pin "2") (pinfunction "2_2") (pintype "passive"))
    )
    (net (code "44") (name "PWMAL") (class "Default")
      (node (ref "IC1") (pin "2") (pinfunction "PWM1L_2") (pintype "bidirectional"))
      (node (ref "PWM") (pin "10") (pinfunction "10_10") (pintype "passive"))
      (node (ref "PWM") (pin "9") (pinfunction "9_9") (pintype "passive"))
      (node (ref "R27") (pin "2") (pinfunction "2_2") (pintype "passive"))
    )
    (net (code "45") (name "PWMBH") (class "Default")
      (node (ref "IC1") (pin "1") (pinfunction "PWM2H_1") (pintype "bidirectional"))
      (node (ref "PWM") (pin "7") (pinfunction "7_7") (pintype "passive"))
      (node (ref "PWM") (pin "8") (pinfunction "8_8") (pintype "passive"))
      (node (ref "R28") (pin "2") (pinfunction "2_2") (pintype "passive"))
    )
    (net (code "46") (name "PWMBL") (class "Default")
      (node (ref "IC1") (pin "40") (pinfunction "PWM2L_40") (pintype "bidirectional"))
      (node (ref "PWM") (pin "5") (pinfunction "5_5") (pintype "passive"))
      (node (ref "PWM") (pin "6") (pinfunction "6_6") (pintype "passive"))
      (node (ref "R29") (pin "2") (pinfunction "2_2") (pintype "passive"))
    )
    (net (code "47") (name "PWMCH") (class "Default")
      (node (ref "IC1") (pin "39") (pinfunction "PWM3H_39") (pintype "bidirectional"))
      (node (ref "PWM") (pin "3") (pinfunction "3_3") (pintype "passive"))
      (node (ref "PWM") (pin "4") (pinfunction "4_4") (pintype "passive"))
      (node (ref "R30") (pin "2") (pinfunction "2_2") (pintype "passive"))
    )
    (net (code "48") (name "PWMCL") (class "Default")
      (node (ref "IC1") (pin "38") (pinfunction "PWM3L_38") (pintype "bidirectional"))
      (node (ref "PWM") (pin "1") (pinfunction "1_1") (pintype "passive"))
      (node (ref "PWM") (pin "2") (pinfunction "2_2") (pintype "passive"))
      (node (ref "R31") (pin "2") (pinfunction "2_2") (pintype "passive"))
    )
    (net (code "49") (name "SENSEA") (class "Default")
      (node (ref "QAL0") (pin "2") (pinfunction "S_2") (pintype "bidirectional"))
      (node (ref "QAL1") (pin "2") (pinfunction "S_2") (pintype "bidirectional"))
      (node (ref "R1") (pin "2") (pinfunction "2_2") (pintype "passive"))
      (node (ref "R7") (pin "2") (pinfunction "2_2") (pintype "passive"))
      (node (ref "RSA") (pin "2") (pinfunction "2_2") (pintype "passive"))
    )
    (net (code "50") (name "SENSEB") (class "Default")
      (node (ref "IC2") (pin "3") (pinfunction "IN+1_3") (pintype "bidirectional"))
      (node (ref "QBL0") (pin "2") (pinfunction "S_2") (pintype "bidirectional"))
      (node (ref "QBL1") (pin "2") (pinfunction "S_2") (pintype "bidirectional"))
      (node (ref "R14") (pin "2") (pinfunction "2_2") (pintype "passive"))
      (node (ref "R5") (pin "2") (pinfunction "2_2") (pintype "passive"))
      (node (ref "R8") (pin "2") (pinfunction "2_2") (pintype "passive"))
      (node (ref "RSB") (pin "2") (pinfunction "2_2") (pintype "passive"))
    )
    (net (code "51") (name "SENSEBHIGH") (class "Default")
      (node (ref "IC1") (pin "12") (pinfunction "ISENSE2+_12") (pintype "bidirectional"))
      (node (ref "R8") (pin "1") (pinfunction "1_1") (pintype "passive"))
    )
    (net (code "52") (name "SENSEBLOW") (class "Default")
      (node (ref "IC1") (pin "11") (pinfunction "ISENSE2-_11") (pintype "bidirectional"))
      (node (ref "R10") (pin "1") (pinfunction "1_1") (pintype "passive"))
      (node (ref "R11") (pin "2") (pinfunction "2_2") (pintype "passive"))
    )
    (net (code "53") (name "SENSEC") (class "Default")
      (node (ref "IC2") (pin "5") (pinfunction "IN+2_5") (pintype "bidirectional"))
      (node (ref "QCL0") (pin "2") (pinfunction "S_2") (pintype "bidirectional"))
      (node (ref "QCL1") (pin "2") (pinfunction "S_2") (pintype "bidirectional"))
      (node (ref "R12") (pin "2") (pinfunction "2_2") (pintype "passive"))
      (node (ref "R17") (pin "2") (pinfunction "2_2") (pintype "passive"))
      (node (ref "R6") (pin "2") (pinfunction "2_2") (pintype "passive"))
      (node (ref "RSC") (pin "2") (pinfunction "2_2") (pintype "passive"))
    )
    (net (code "54") (name "SENSECHIGH") (class "Default")
      (node (ref "IC1") (pin "9") (pinfunction "ISENSE3+_9") (pintype "bidirectional"))
      (node (ref "R12") (pin "1") (pinfunction "1_1") (pintype "passive"))
    )
    (net (code "55") (name "SENSECLOW") (class "Default")
      (node (ref "IC1") (pin "8") (pinfunction "ISENSE3-_8") (pintype "bidirectional"))
      (node (ref "R15") (pin "1") (pinfunction "1_1") (pintype "passive"))
      (node (ref "R16") (pin "2") (pinfunction "2_2") (pintype "passive"))
    )
    (net (code "56") (name "SENSESUMHIGH") (class "Default")
      (node (ref "IC1") (pin "16") (pinfunction "I_SENSE1+_16") (pintype "bidirectional"))
      (node (ref "R1") (pin "1") (pinfunction "1_1") (pintype "passive"))
      (node (ref "R5") (pin "1") (pinfunction "1_1") (pintype "passive"))
      (node (ref "R6") (pin "1") (pinfunction "1_1") (pintype "passive"))
    )
    (net (code "57") (name "SENSESUMLOW") (class "Default")
      (node (ref "IC1") (pin "15") (pinfunction "I_SENSE1-_15") (pintype "bidirectional"))
      (node (ref "R3") (pin "1") (pinfunction "1_1") (pintype "passive"))
      (node (ref "R4") (pin "2") (pinfunction "2_2") (pintype "passive"))
    )
    (net (code "58") (name "SW0") (class "Default")
      (node (ref "GPIO") (pin "2") (pinfunction "2_2") (pintype "passive"))
      (node (ref "R39") (pin "1") (pinfunction "1_1") (pintype "passive"))
      (node (ref "SW0") (pin "3") (pinfunction "3_3") (pintype "passive"))
    )
    (net (code "59") (name "SW1") (class "Default")
      (node (ref "GPIO") (pin "1") (pinfunction "1_1") (pintype "passive"))
      (node (ref "R40") (pin "1") (pinfunction "1_1") (pintype "passive"))
      (node (ref "SW1") (pin "3") (pinfunction "3_3") (pintype "passive"))
    )
    (net (code "60") (name "VBA") (class "Default")
      (node (ref "BSA") (pin "1") (pinfunction "1_1") (pintype "passive"))
      (node (ref "C2") (pin "1") (pinfunction "1_1") (pintype "passive"))
      (node (ref "C3") (pin "1") (pinfunction "1_1") (pintype "passive"))
      (node (ref "DA") (pin "C") (pinfunction "C_C") (pintype "passive"))
      (node (ref "IC1") (pin "29") (pinfunction "VBA_29") (pintype "bidirectional"))
      (node (ref "VBA") (pin "1") (pinfunction "1_1") (pintype "passive"))
    )
    (net (code "61") (name "VBB") (class "Default")
      (node (ref "BSB") (pin "1") (pinfunction "1_1") (pintype "passive"))
      (node (ref "C5") (pin "1") (pinfunction "1_1") (pintype "passive"))
      (node (ref "C6") (pin "1") (pinfunction "1_1") (pintype "passive"))
      (node (ref "DB") (pin "C") (pinfunction "C_C") (pintype "passive"))
      (node (ref "IC1") (pin "28") (pinfunction "VBB_28") (pintype "bidirectional"))
      (node (ref "VBB") (pin "1") (pinfunction "1_1") (pintype "passive"))
    )
    (net (code "62") (name "VBC") (class "Default")
      (node (ref "BSC") (pin "1") (pinfunction "1_1") (pintype "passive"))
      (node (ref "C8") (pin "1") (pinfunction "1_1") (pintype "passive"))
      (node (ref "C9") (pin "1") (pinfunction "1_1") (pintype "passive"))
      (node (ref "DC") (pin "C") (pinfunction "C_C") (pintype "passive"))
      (node (ref "IC1") (pin "27") (pinfunction "VBC_27") (pintype "bidirectional"))
      (node (ref "VBC") (pin "1") (pinfunction "1_1") (pintype "passive"))
    )
    (net (code "63") (name "VCC") (class "Default")
      (node (ref "C10") (pin "+") (pinfunction "+_+") (pintype "passive"))
      (node (ref "CA") (pin "+") (pinfunction "+_+") (pintype "passive"))
      (node (ref "CB") (pin "+") (pinfunction "+_+") (pintype "passive"))
      (node (ref "CC") (pin "+") (pinfunction "+_+") (pintype "passive"))
      (node (ref "HBH0") (pin "3") (pinfunction "D_3") (pintype "bidirectional"))
      (node (ref "IC1") (pin "32") (pinfunction "VDD_32") (pintype "power_in"))
      (node (ref "QAH0") (pin "3") (pinfunction "D_3") (pintype "bidirectional"))
      (node (ref "QAH1") (pin "3") (pinfunction "D_3") (pintype "bidirectional"))
      (node (ref "QBH1") (pin "3") (pinfunction "D_3") (pintype "bidirectional"))
      (node (ref "QCH0") (pin "3") (pinfunction "D_3") (pintype "bidirectional"))
      (node (ref "QCH1") (pin "3") (pinfunction "D_3") (pintype "bidirectional"))
      (node (ref "R36") (pin "2") (pinfunction "2_2") (pintype "passive"))
      (node (ref "R41") (pin "2") (pinfunction "2_2") (pintype "passive"))
      (node (ref "VBAT") (pin "1") (pinfunction "1_1") (pintype "passive"))
      (node (ref "VBAT") (pin "2") (pinfunction "2_2") (pintype "passive"))
    )
    (net (code "64") (name "VREF") (class "Default")
      (node (ref "CURRENT") (pin "5") (pinfunction "5_5") (pintype "passive"))
      (node (ref "CURRENT") (pin "6") (pinfunction "6_6") (pintype "passive"))
      (node (ref "R24") (pin "2") (pinfunction "2_2") (pintype "passive"))
      (node (ref "R25") (pin "1") (pinfunction "1_1") (pintype "passive"))
    )
    (net (code "65") (name "unconnected-(SW0-Pad2)") (class "Default")
      (node (ref "SW0") (pin "2") (pinfunction "2_2") (pintype "passive"))
    )
    (net (code "66") (name "unconnected-(SW0-Pad4)") (class "Default")
      (node (ref "SW0") (pin "4") (pinfunction "4_4") (pintype "passive"))
    )
    (net (code "67") (name "unconnected-(SW1-Pad2)") (class "Default")
      (node (ref "SW1") (pin "2") (pinfunction "2_2") (pintype "passive"))
    )
    (net (code "68") (name "unconnected-(SW1-Pad4)") (class "Default")
      (node (ref "SW1") (pin "4") (pinfunction "4_4") (pintype "passive"))
    )
  )
)
